# 001-0002_beaglebone_cape_board.net
KiCad netlist of a schematic drawn in Altium Designer
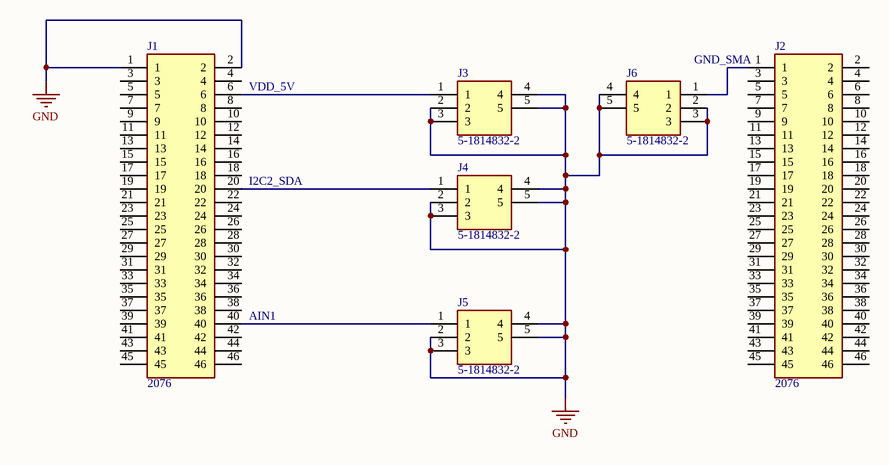
[diagram p0: 001-0002_beaglebone_cape_board.SchDoc]

(export (version "E")
  (design (tool "Eeschema 10.0.6"))
  (components
    (comp (ref "J1")
      (value "2076")
      (footprint "HDRV46W64P254_2X23_5842X500X874P")
      (description "Adafruit Accessories 2x23 Male Headers for BeagleBone Black - Two Pack")
      (fields (field (name "MOUSER PART NUMBER") "485-2076"))
      (libsource (lib "default") (part "2076"))
    )
    (comp (ref "J2")
      (value "2076")
      (footprint "HDRV46W64P254_2X23_5842X500X874P")
      (description "Adafruit Accessories 2x23 Male Headers for BeagleBone Black - Two Pack")
      (fields (field (name "MOUSER PART NUMBER") "485-2076"))
      (libsource (lib "default") (part "2076"))
    )
    (comp (ref "J3")
      (value "5-1814832-2")
      (footprint "5-1814832-2")
      (description "SMA Connector Jack, Female Socket 50 Ohms Through Hole Solder")
      (fields (field (name "MOUSER PART NUMBER") "571-5-1814832-2"))
      (libsource (lib "") (part "5-1814832-2_1"))
    )
    (comp (ref "J4")
      (value "5-1814832-2")
      (footprint "5-1814832-2")
      (description "SMA Connector Jack, Female Socket 50 Ohms Through Hole Solder")
      (fields (field (name "MOUSER PART NUMBER") "571-5-1814832-2"))
      (libsource (lib "") (part "5-1814832-2_1"))
    )
    (comp (ref "J5")
      (value "5-1814832-2")
      (footprint "5-1814832-2")
      (description "SMA Connector Jack, Female Socket 50 Ohms Through Hole Solder")
      (fields (field (name "MOUSER PART NUMBER") "571-5-1814832-2"))
      (libsource (lib "") (part "5-1814832-2_1"))
    )
    (comp (ref "J6")
      (value "5-1814832-2")
      (footprint "5-1814832-2")
      (description "SMA Connector Jack, Female Socket 50 Ohms Through Hole Solder")
      (fields (field (name "MOUSER PART NUMBER") "571-5-1814832-2"))
      (libsource (lib "default") (part "5-1814832-2"))
    )
  )
  (nets
    (net (code "1") (name "GND") (class "Default")
      (node (ref "J1") (pin "1") (pinfunction "1_1") (pintype "passive"))
      (node (ref "J1") (pin "2") (pinfunction "2_2") (pintype "passive"))
      (node (ref "J3") (pin "2") (pinfunction "2_2") (pintype "passive"))
      (node (ref "J3") (pin "3") (pinfunction "3_3") (pintype "passive"))
      (node (ref "J3") (pin "4") (pinfunction "4_4") (pintype "passive"))
      (node (ref "J3") (pin "5") (pinfunction "5_5") (pintype "passive"))
      (node (ref "J4") (pin "2") (pinfunction "2_2") (pintype "passive"))
      (node (ref "J4") (pin "3") (pinfunction "3_3") (pintype "passive"))
      (node (ref "J4") (pin "4") (pinfunction "4_4") (pintype "passive"))
      (node (ref "J4") (pin "5") (pinfunction "5_5") (pintype "passive"))
      (node (ref "J5") (pin "2") (pinfunction "2_2") (pintype "passive"))
      (node (ref "J5") (pin "3") (pinfunction "3_3") (pintype "passive"))
      (node (ref "J5") (pin "4") (pinfunction "4_4") (pintype "passive"))
      (node (ref "J5") (pin "5") (pinfunction "5_5") (pintype "passive"))
      (node (ref "J6") (pin "2") (pinfunction "2_2") (pintype "passive"))
      (node (ref "J6") (pin "3") (pinfunction "3_3") (pintype "passive"))
      (node (ref "J6") (pin "4") (pinfunction "4_4") (pintype "passive"))
      (node (ref "J6") (pin "5") (pinfunction "5_5") (pintype "passive"))
    )
    (net (code "2") (name "Net-(J1-Pad6)") (class "Default")
      (node (ref "J1") (pin "6") (pinfunction "6_6") (pintype "passive"))
      (node (ref "J3") (pin "1") (pinfunction "1_1") (pintype "passive"))
    )
    (net (code "3") (name "Net-(J1-Pad20)") (class "Default")
      (node (ref "J1") (pin "20") (pinfunction "20_20") (pintype "passive"))
      (node (ref "J4") (pin "1") (pinfunction "1_1") (pintype "passive"))
    )
    (net (code "4") (name "Net-(J1-Pad40)") (class "Default")
      (node (ref "J1") (pin "40") (pinfunction "40_40") (pintype "passive"))
      (node (ref "J5") (pin "1") (pinfunction "1_1") (pintype "passive"))
    )
    (net (code "5") (name "Net-(J2-Pad1)") (class "Default")
      (node (ref "J2") (pin "1") (pinfunction "1_1") (pintype "passive"))
      (node (ref "J6") (pin "1") (pinfunction "1_1") (pintype "passive"))
    )
    (net (code "6") (name "unconnected-(J1-Pad3)") (class "Default")
      (node (ref "J1") (pin "3") (pinfunction "3_3") (pintype "passive"))
    )
    (net (code "7") (name "unconnected-(J1-Pad4)") (class "Default")
      (node (ref "J1") (pin "4") (pinfunction "4_4") (pintype "passive"))
    )
    (net (code "8") (name "unconnected-(J1-Pad5)") (class "Default")
      (node (ref "J1") (pin "5") (pinfunction "5_5") (pintype "passive"))
    )
    (net (code "9") (name "unconnected-(J1-Pad7)") (class "Default")
      (node (ref "J1") (pin "7") (pinfunction "7_7") (pintype "passive"))
    )
    (net (code "10") (name "unconnected-(J1-Pad8)") (class "Default")
      (node (ref "J1") (pin "8") (pinfunction "8_8") (pintype "passive"))
    )
    (net (code "11") (name "unconnected-(J1-Pad9)") (class "Default")
      (node (ref "J1") (pin "9") (pinfunction "9_9") (pintype "passive"))
    )
    (net (code "12") (name "unconnected-(J1-Pad10)") (class "Default")
      (node (ref "J1") (pin "10") (pinfunction "10_10") (pintype "passive"))
    )
    (net (code "13") (name "unconnected-(J1-Pad11)") (class "Default")
      (node (ref "J1") (pin "11") (pinfunction "11_11") (pintype "passive"))
    )
    (net (code "14") (name "unconnected-(J1-Pad12)") (class "Default")
      (node (ref "J1") (pin "12") (pinfunction "12_12") (pintype "passive"))
    )
    (net (code "15") (name "unconnected-(J1-Pad13)") (class "Default")
      (node (ref "J1") (pin "13") (pinfunction "13_13") (pintype "passive"))
    )
    (net (code "16") (name "unconnected-(J1-Pad14)") (class "Default")
      (node (ref "J1") (pin "14") (pinfunction "14_14") (pintype "passive"))
    )
    (net (code "17") (name "unconnected-(J1-Pad15)") (class "Default")
      (node (ref "J1") (pin "15") (pinfunction "15_15") (pintype "passive"))
    )
    (net (code "18") (name "unconnected-(J1-Pad16)") (class "Default")
      (node (ref "J1") (pin "16") (pinfunction "16_16") (pintype "passive"))
    )
    (net (code "19") (name "unconnected-(J1-Pad17)") (class "Default")
      (node (ref "J1") (pin "17") (pinfunction "17_17") (pintype "passive"))
    )
    (net (code "20") (name "unconnected-(J1-Pad18)") (class "Default")
      (node (ref "J1") (pin "18") (pinfunction "18_18") (pintype "passive"))
    )
    (net (code "21") (name "unconnected-(J1-Pad19)") (class "Default")
      (node (ref "J1") (pin "19") (pinfunction "19_19") (pintype "passive"))
    )
    (net (code "22") (name "unconnected-(J1-Pad21)") (class "Default")
      (node (ref "J1") (pin "21") (pinfunction "21_21") (pintype "passive"))
    )
    (net (code "23") (name "unconnected-(J1-Pad22)") (class "Default")
      (node (ref "J1") (pin "22") (pinfunction "22_22") (pintype "passive"))
    )
    (net (code "24") (name "unconnected-(J1-Pad23)") (class "Default")
      (node (ref "J1") (pin "23") (pinfunction "23_23") (pintype "passive"))
    )
    (net (code "25") (name "unconnected-(J1-Pad24)") (class "Default")
      (node (ref "J1") (pin "24") (pinfunction "24_24") (pintype "passive"))
    )
    (net (code "26") (name "unconnected-(J1-Pad25)") (class "Default")
      (node (ref "J1") (pin "25") (pinfunction "25_25") (pintype "passive"))
    )
    (net (code "27") (name "unconnected-(J1-Pad26)") (class "Default")
      (node (ref "J1") (pin "26") (pinfunction "26_26") (pintype "passive"))
    )
    (net (code "28") (name "unconnected-(J1-Pad27)") (class "Default")
      (node (ref "J1") (pin "27") (pinfunction "27_27") (pintype "passive"))
    )
    (net (code "29") (name "unconnected-(J1-Pad28)") (class "Default")
      (node (ref "J1") (pin "28") (pinfunction "28_28") (pintype "passive"))
    )
    (net (code "30") (name "unconnected-(J1-Pad29)") (class "Default")
      (node (ref "J1") (pin "29") (pinfunction "29_29") (pintype "passive"))
    )
    (net (code "31") (name "unconnected-(J1-Pad30)") (class "Default")
      (node (ref "J1") (pin "30") (pinfunction "30_30") (pintype "passive"))
    )
    (net (code "32") (name "unconnected-(J1-Pad31)") (class "Default")
      (node (ref "J1") (pin "31") (pinfunction "31_31") (pintype "passive"))
    )
    (net (code "33") (name "unconnected-(J1-Pad32)") (class "Default")
      (node (ref "J1") (pin "32") (pinfunction "32_32") (pintype "passive"))
    )
    (net (code "34") (name "unconnected-(J1-Pad33)") (class "Default")
      (node (ref "J1") (pin "33") (pinfunction "33_33") (pintype "passive"))
    )
    (net (code "35") (name "unconnected-(J1-Pad34)") (class "Default")
      (node (ref "J1") (pin "34") (pinfunction "34_34") (pintype "passive"))
    )
    (net (code "36") (name "unconnected-(J1-Pad35)") (class "Default")
      (node (ref "J1") (pin "35") (pinfunction "35_35") (pintype "passive"))
    )
    (net (code "37") (name "unconnected-(J1-Pad36)") (class "Default")
      (node (ref "J1") (pin "36") (pinfunction "36_36") (pintype "passive"))
    )
    (net (code "38") (name "unconnected-(J1-Pad37)") (class "Default")
      (node (ref "J1") (pin "37") (pinfunction "37_37") (pintype "passive"))
    )
    (net (code "39") (name "unconnected-(J1-Pad38)") (class "Default")
      (node (ref "J1") (pin "38") (pinfunction "38_38") (pintype "passive"))
    )
    (net (code "40") (name "unconnected-(J1-Pad39)") (class "Default")
      (node (ref "J1") (pin "39") (pinfunction "39_39") (pintype "passive"))
    )
    (net (code "41") (name "unconnected-(J1-Pad41)") (class "Default")
      (node (ref "J1") (pin "41") (pinfunction "41_41") (pintype "passive"))
    )
    (net (code "42") (name "unconnected-(J1-Pad42)") (class "Default")
      (node (ref "J1") (pin "42") (pinfunction "42_42") (pintype "passive"))
    )
    (net (code "43") (name "unconnected-(J1-Pad43)") (class "Default")
      (node (ref "J1") (pin "43") (pinfunction "43_43") (pintype "passive"))
    )
    (net (code "44") (name "unconnected-(J1-Pad44)") (class "Default")
      (node (ref "J1") (pin "44") (pinfunction "44_44") (pintype "passive"))
    )
    (net (code "45") (name "unconnected-(J1-Pad45)") (class "Default")
      (node (ref "J1") (pin "45") (pinfunction "45_45") (pintype "passive"))
    )
    (net (code "46") (name "unconnected-(J1-Pad46)") (class "Default")
      (node (ref "J1") (pin "46") (pinfunction "46_46") (pintype "passive"))
    )
    (net (code "47") (name "unconnected-(J2-Pad2)") (class "Default")
      (node (ref "J2") (pin "2") (pinfunction "2_2") (pintype "passive"))
    )
    (net (code "48") (name "unconnected-(J2-Pad3)") (class "Default")
      (node (ref "J2") (pin "3") (pinfunction "3_3") (pintype "passive"))
    )
    (net (code "49") (name "unconnected-(J2-Pad4)") (class "Default")
      (node (ref "J2") (pin "4") (pinfunction "4_4") (pintype "passive"))
    )
    (net (code "50") (name "unconnected-(J2-Pad5)") (class "Default")
      (node (ref "J2") (pin "5") (pinfunction "5_5") (pintype "passive"))
    )
    (net (code "51") (name "unconnected-(J2-Pad6)") (class "Default")
      (node (ref "J2") (pin "6") (pinfunction "6_6") (pintype "passive"))
    )
    (net (code "52") (name "unconnected-(J2-Pad7)") (class "Default")
      (node (ref "J2") (pin "7") (pinfunction "7_7") (pintype "passive"))
    )
    (net (code "53") (name "unconnected-(J2-Pad8)") (class "Default")
      (node (ref "J2") (pin "8") (pinfunction "8_8") (pintype "passive"))
    )
    (net (code "54") (name "unconnected-(J2-Pad9)") (class "Default")
      (node (ref "J2") (pin "9") (pinfunction "9_9") (pintype "passive"))
    )
    (net (code "55") (name "unconnected-(J2-Pad10)") (class "Default")
      (node (ref "J2") (pin "10") (pinfunction "10_10") (pintype "passive"))
    )
    (net (code "56") (name "unconnected-(J2-Pad11)") (class "Default")
      (node (ref "J2") (pin "11") (pinfunction "11_11") (pintype "passive"))
    )
    (net (code "57") (name "unconnected-(J2-Pad12)") (class "Default")
      (node (ref "J2") (pin "12") (pinfunction "12_12") (pintype "passive"))
    )
    (net (code "58") (name "unconnected-(J2-Pad13)") (class "Default")
      (node (ref "J2") (pin "13") (pinfunction "13_13") (pintype "passive"))
    )
    (net (code "59") (name "unconnected-(J2-Pad14)") (class "Default")
      (node (ref "J2") (pin "14") (pinfunction "14_14") (pintype "passive"))
    )
    (net (code "60") (name "unconnected-(J2-Pad15)") (class "Default")
      (node (ref "J2") (pin "15") (pinfunction "15_15") (pintype "passive"))
    )
    (net (code "61") (name "unconnected-(J2-Pad16)") (class "Default")
      (node (ref "J2") (pin "16") (pinfunction "16_16") (pintype "passive"))
    )
    (net (code "62") (name "unconnected-(J2-Pad17)") (class "Default")
      (node (ref "J2") (pin "17") (pinfunction "17_17") (pintype "passive"))
    )
    (net (code "63") (name "unconnected-(J2-Pad18)") (class "Default")
      (node (ref "J2") (pin "18") (pinfunction "18_18") (pintype "passive"))
    )
    (net (code "64") (name "unconnected-(J2-Pad19)") (class "Default")
      (node (ref "J2") (pin "19") (pinfunction "19_19") (pintype "passive"))
    )
    (net (code "65") (name "unconnected-(J2-Pad20)") (class "Default")
      (node (ref "J2") (pin "20") (pinfunction "20_20") (pintype "passive"))
    )
    (net (code "66") (name "unconnected-(J2-Pad21)") (class "Default")
      (node (ref "J2") (pin "21") (pinfunction "21_21") (pintype "passive"))
    )
    (net (code "67") (name "unconnected-(J2-Pad22)") (class "Default")
      (node (ref "J2") (pin "22") (pinfunction "22_22") (pintype "passive"))
    )
    (net (code "68") (name "unconnected-(J2-Pad23)") (class "Default")
      (node (ref "J2") (pin "23") (pinfunction "23_23") (pintype "passive"))
    )
    (net (code "69") (name "unconnected-(J2-Pad24)") (class "Default")
      (node (ref "J2") (pin "24") (pinfunction "24_24") (pintype "passive"))
    )
    (net (code "70") (name "unconnected-(J2-Pad25)") (class "Default")
      (node (ref "J2") (pin "25") (pinfunction "25_25") (pintype "passive"))
    )
    (net (code "71") (name "unconnected-(J2-Pad26)") (class "Default")
      (node (ref "J2") (pin "26") (pinfunction "26_26") (pintype "passive"))
    )
    (net (code "72") (name "unconnected-(J2-Pad27)") (class "Default")
      (node (ref "J2") (pin "27") (pinfunction "27_27") (pintype "passive"))
    )
    (net (code "73") (name "unconnected-(J2-Pad28)") (class "Default")
      (node (ref "J2") (pin "28") (pinfunction "28_28") (pintype "passive"))
    )
    (net (code "74") (name "unconnected-(J2-Pad29)") (class "Default")
      (node (ref "J2") (pin "29") (pinfunction "29_29") (pintype "passive"))
    )
    (net (code "75") (name "unconnected-(J2-Pad30)") (class "Default")
      (node (ref "J2") (pin "30") (pinfunction "30_30") (pintype "passive"))
    )
    (net (code "76") (name "unconnected-(J2-Pad31)") (class "Default")
      (node (ref "J2") (pin "31") (pinfunction "31_31") (pintype "passive"))
    )
    (net (code "77") (name "unconnected-(J2-Pad32)") (class "Default")
      (node (ref "J2") (pin "32") (pinfunction "32_32") (pintype "passive"))
    )
    (net (code "78") (name "unconnected-(J2-Pad33)") (class "Default")
      (node (ref "J2") (pin "33") (pinfunction "33_33") (pintype "passive"))
    )
    (net (code "79") (name "unconnected-(J2-Pad34)") (class "Default")
      (node (ref "J2") (pin "34") (pinfunction "34_34") (pintype "passive"))
    )
    (net (code "80") (name "unconnected-(J2-Pad35)") (class "Default")
      (node (ref "J2") (pin "35") (pinfunction "35_35") (pintype "passive"))
    )
    (net (code "81") (name "unconnected-(J2-Pad36)") (class "Default")
      (node (ref "J2") (pin "36") (pinfunction "36_36") (pintype "passive"))
    )
    (net (code "82") (name "unconnected-(J2-Pad37)") (class "Default")
      (node (ref "J2") (pin "37") (pinfunction "37_37") (pintype "passive"))
    )
    (net (code "83") (name "unconnected-(J2-Pad38)") (class "Default")
      (node (ref "J2") (pin "38") (pinfunction "38_38") (pintype "passive"))
    )
    (net (code "84") (name "unconnected-(J2-Pad39)") (class "Default")
      (node (ref "J2") (pin "39") (pinfunction "39_39") (pintype "passive"))
    )
    (net (code "85") (name "unconnected-(J2-Pad40)") (class "Default")
      (node (ref "J2") (pin "40") (pinfunction "40_40") (pintype "passive"))
    )
    (net (code "86") (name "unconnected-(J2-Pad41)") (class "Default")
      (node (ref "J2") (pin "41") (pinfunction "41_41") (pintype "passive"))
    )
    (net (code "87") (name "unconnected-(J2-Pad42)") (class "Default")
      (node (ref "J2") (pin "42") (pinfunction "42_42") (pintype "passive"))
    )
    (net (code "88") (name "unconnected-(J2-Pad43)") (class "Default")
      (node (ref "J2") (pin "43") (pinfunction "43_43") (pintype "passive"))
    )
    (net (code "89") (name "unconnected-(J2-Pad44)") (class "Default")
      (node (ref "J2") (pin "44") (pinfunction "44_44") (pintype "passive"))
    )
    (net (code "90") (name "unconnected-(J2-Pad45)") (class "Default")
      (node (ref "J2") (pin "45") (pinfunction "45_45") (pintype "passive"))
    )
    (net (code "91") (name "unconnected-(J2-Pad46)") (class "Default")
      (node (ref "J2") (pin "46") (pinfunction "46_46") (pintype "passive"))
    )
  )
)
